# Hardware_Comp_V1_4.net
KiCad netlist of a schematic drawn in EAGLE
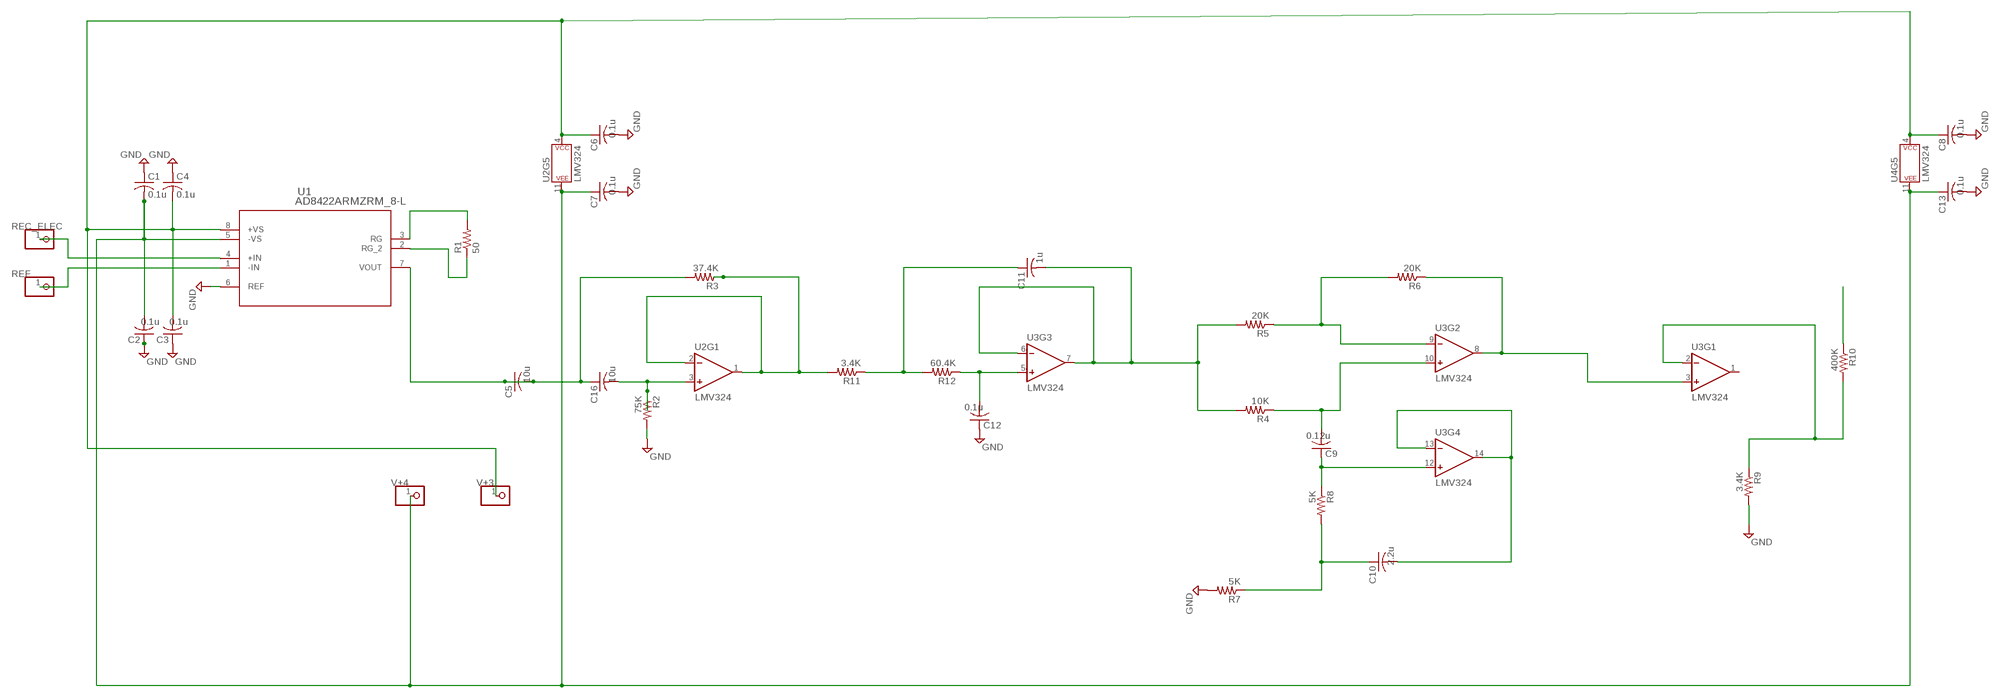
[diagram p0: schematic, sheet 1]

(export (version "E")
  (design (tool "Eeschema 10.0.6"))
  (components
    (comp (ref "9V-")
      (value "PINHD-1X1")
      (footprint "eagle-import:1X01")
      (libsource (lib "eagle-import") (part "PINHD-1X1"))
    )
    (comp (ref "C1")
      (value "0.1u")
      (footprint "eagle-import:C0603")
      (libsource (lib "eagle-import") (part "C-USC0603"))
    )
    (comp (ref "C2")
      (value "0.1u")
      (footprint "eagle-import:C0603")
      (libsource (lib "eagle-import") (part "C-USC0603"))
    )
    (comp (ref "C3")
      (value "0.1u")
      (footprint "eagle-import:C0603")
      (libsource (lib "eagle-import") (part "C-USC0603"))
    )
    (comp (ref "C4")
      (value "0.1u")
      (footprint "eagle-import:C0603")
      (libsource (lib "eagle-import") (part "C-USC0603"))
    )
    (comp (ref "C5")
      (value "10u")
      (footprint "eagle-import:C0603")
      (libsource (lib "eagle-import") (part "C-USC0603"))
    )
    (comp (ref "C6")
      (value "0.1u")
      (footprint "eagle-import:C0603")
      (libsource (lib "eagle-import") (part "C-USC0603"))
    )
    (comp (ref "C7")
      (value "0.1u")
      (footprint "eagle-import:C0603")
      (libsource (lib "eagle-import") (part "C-USC0603"))
    )
    (comp (ref "C8")
      (value "0.1u")
      (footprint "eagle-import:C0603")
      (libsource (lib "eagle-import") (part "C-USC0603"))
    )
    (comp (ref "C9")
      (value "0.12u")
      (footprint "eagle-import:C0603")
      (libsource (lib "eagle-import") (part "C-USC0603"))
    )
    (comp (ref "C10")
      (value "2.2u")
      (footprint "eagle-import:C0603")
      (libsource (lib "eagle-import") (part "C-USC0603"))
    )
    (comp (ref "C11")
      (value "1u")
      (footprint "eagle-import:C0603")
      (libsource (lib "eagle-import") (part "C-USC0603"))
    )
    (comp (ref "C12")
      (value "0.1u")
      (footprint "eagle-import:C0603")
      (libsource (lib "eagle-import") (part "C-USC0603"))
    )
    (comp (ref "C13")
      (value "0.1u")
      (footprint "eagle-import:C0603")
      (libsource (lib "eagle-import") (part "C-USC0603"))
    )
    (comp (ref "C16")
      (value "10u")
      (footprint "eagle-import:C0603")
      (libsource (lib "eagle-import") (part "C-USC0603"))
    )
    (comp (ref "JP1")
      (value "PINHD-1X1")
      (footprint "eagle-import:1X01")
      (libsource (lib "eagle-import") (part "PINHD-1X1"))
    )
    (comp (ref "JP2")
      (value "PINHD-1X1")
      (footprint "eagle-import:1X01")
      (libsource (lib "eagle-import") (part "PINHD-1X1"))
    )
    (comp (ref "JP3")
      (value "PINHD-1X1")
      (footprint "eagle-import:1X01")
      (libsource (lib "eagle-import") (part "PINHD-1X1"))
    )
    (comp (ref "R1")
      (value "50")
      (footprint "eagle-import:R0603")
      (libsource (lib "eagle-import") (part "R-US_R0603"))
    )
    (comp (ref "R2")
      (value "75K")
      (footprint "eagle-import:R0603")
      (libsource (lib "eagle-import") (part "R-US_R0603"))
    )
    (comp (ref "R3")
      (value "37.4K")
      (footprint "eagle-import:R0603")
      (libsource (lib "eagle-import") (part "R-US_R0603"))
    )
    (comp (ref "R4")
      (value "10K")
      (footprint "eagle-import:R0603")
      (libsource (lib "eagle-import") (part "R-US_R0603"))
    )
    (comp (ref "R5")
      (value "20K")
      (footprint "eagle-import:R0603")
      (libsource (lib "eagle-import") (part "R-US_R0603"))
    )
    (comp (ref "R6")
      (value "20K")
      (footprint "eagle-import:R0603")
      (libsource (lib "eagle-import") (part "R-US_R0603"))
    )
    (comp (ref "R7")
      (value "5K")
      (footprint "eagle-import:R0603")
      (libsource (lib "eagle-import") (part "R-US_R0603"))
    )
    (comp (ref "R8")
      (value "5K")
      (footprint "eagle-import:R0603")
      (libsource (lib "eagle-import") (part "R-US_R0603"))
    )
    (comp (ref "R9")
      (value "3.4K")
      (footprint "eagle-import:R0603")
      (libsource (lib "eagle-import") (part "R-US_R0603"))
    )
    (comp (ref "R10")
      (value "400K")
      (footprint "eagle-import:R0603")
      (libsource (lib "eagle-import") (part "R-US_R0603"))
    )
    (comp (ref "R11")
      (value "3.4K")
      (footprint "eagle-import:R0603")
      (libsource (lib "eagle-import") (part "R-US_R0603"))
    )
    (comp (ref "R12")
      (value "60.4K")
      (footprint "eagle-import:R0603")
      (libsource (lib "eagle-import") (part "R-US_R0603"))
    )
    (comp (ref "U1")
      (value "AD8422ARMZRM_8-L")
      (footprint "eagle-import:RM_8-L")
      (fields (field (name "MANUFACTURER_PART_NUMBER") "AD8422ARMZ"))
      (libsource (lib "eagle-import") (part "AD8422ARMZRM_8-L"))
    )
    (comp (ref "U2")
      (value "LMV324")
      (footprint "eagle-import:SO14")
      (libsource (lib "eagle-import") (part "LMV324"))
    )
    (comp (ref "U3")
      (value "LMV324")
      (footprint "eagle-import:SO14")
      (libsource (lib "eagle-import") (part "LMV324"))
    )
    (comp (ref "U4")
      (value "LMV324")
      (footprint "eagle-import:SO14")
      (libsource (lib "eagle-import") (part "LMV324"))
    )
  )
  (nets
    (net (code "1") (name "/REC_ELEC") (class "Default")
      (node (ref "JP1") (pin "1") (pinfunction "1_1") (pintype "passive"))
      (node (ref "U1") (pin "4") (pinfunction "+IN_4") (pintype "passive"))
    )
    (net (code "2") (name "/REF") (class "Default")
      (node (ref "JP2") (pin "1") (pinfunction "1_1") (pintype "passive"))
      (node (ref "U1") (pin "1") (pinfunction "-IN_1") (pintype "passive"))
    )
    (net (code "3") (name "/V+3") (class "Default")
      (node (ref "9V-") (pin "1") (pinfunction "1_1") (pintype "passive"))
      (node (ref "C3") (pin "2") (pinfunction "2_2") (pintype "passive"))
      (node (ref "C4") (pin "2") (pinfunction "2_2") (pintype "passive"))
      (node (ref "C6") (pin "1") (pinfunction "1_1") (pintype "passive"))
      (node (ref "C8") (pin "1") (pinfunction "1_1") (pintype "passive"))
      (node (ref "U1") (pin "8") (pinfunction "+VS_8") (pintype "passive"))
      (node (ref "U2") (pin "4") (pinfunction "P$V+_4") (pintype "bidirectional"))
      (node (ref "U4") (pin "4") (pinfunction "P$V+_4") (pintype "bidirectional"))
    )
    (net (code "4") (name "/V+4") (class "Default")
      (node (ref "C1") (pin "2") (pinfunction "2_2") (pintype "passive"))
      (node (ref "C13") (pin "1") (pinfunction "1_1") (pintype "passive"))
      (node (ref "C2") (pin "2") (pinfunction "2_2") (pintype "passive"))
      (node (ref "C7") (pin "1") (pinfunction "1_1") (pintype "passive"))
      (node (ref "JP3") (pin "1") (pinfunction "1_1") (pintype "passive"))
      (node (ref "U1") (pin "5") (pinfunction "-VS_5") (pintype "passive"))
      (node (ref "U2") (pin "11") (pinfunction "P$V-_11") (pintype "bidirectional"))
      (node (ref "U4") (pin "11") (pinfunction "P$V-_11") (pintype "bidirectional"))
    )
    (net (code "5") (name "GND") (class "Default")
      (node (ref "C1") (pin "1") (pinfunction "1_1") (pintype "passive"))
      (node (ref "C12") (pin "1") (pinfunction "1_1") (pintype "passive"))
      (node (ref "C13") (pin "2") (pinfunction "2_2") (pintype "passive"))
      (node (ref "C2") (pin "1") (pinfunction "1_1") (pintype "passive"))
      (node (ref "C3") (pin "1") (pinfunction "1_1") (pintype "passive"))
      (node (ref "C4") (pin "1") (pinfunction "1_1") (pintype "passive"))
      (node (ref "C6") (pin "2") (pinfunction "2_2") (pintype "passive"))
      (node (ref "C7") (pin "2") (pinfunction "2_2") (pintype "passive"))
      (node (ref "C8") (pin "2") (pinfunction "2_2") (pintype "passive"))
      (node (ref "R2") (pin "2") (pinfunction "2_2") (pintype "passive"))
      (node (ref "R7") (pin "2") (pinfunction "2_2") (pintype "passive"))
      (node (ref "R9") (pin "2") (pinfunction "2_2") (pintype "passive"))
      (node (ref "U1") (pin "6") (pinfunction "REF_6") (pintype "passive"))
    )
    (net (code "6") (name "Net-(C10-Pad1)") (class "Default")
      (node (ref "C10") (pin "1") (pinfunction "1_1") (pintype "passive"))
      (node (ref "R7") (pin "1") (pinfunction "1_1") (pintype "passive"))
      (node (ref "R8") (pin "2") (pinfunction "2_2") (pintype "passive"))
    )
    (net (code "7") (name "Net-(C11-Pad1)") (class "Default")
      (node (ref "C11") (pin "1") (pinfunction "1_1") (pintype "passive"))
      (node (ref "R11") (pin "1") (pinfunction "1_1") (pintype "passive"))
      (node (ref "R12") (pin "2") (pinfunction "2_2") (pintype "passive"))
    )
    (net (code "8") (name "Net-(U1-RG)") (class "Default")
      (node (ref "R1") (pin "2") (pinfunction "2_2") (pintype "passive"))
      (node (ref "U1") (pin "3") (pinfunction "RG_3") (pintype "passive"))
    )
    (net (code "9") (name "Net-(U1-RG_2)") (class "Default")
      (node (ref "R1") (pin "1") (pinfunction "1_1") (pintype "passive"))
      (node (ref "U1") (pin "2") (pinfunction "RG_2_2") (pintype "passive"))
    )
    (net (code "10") (name "Net-(U1-VOUT)") (class "Default")
      (node (ref "C16") (pin "1") (pinfunction "1_1") (pintype "passive"))
      (node (ref "C5") (pin "1") (pinfunction "1_1") (pintype "passive"))
      (node (ref "C5") (pin "2") (pinfunction "2_2") (pintype "passive"))
      (node (ref "R3") (pin "2") (pinfunction "2_2") (pintype "passive"))
      (node (ref "U1") (pin "7") (pinfunction "VOUT_7") (pintype "passive"))
    )
    (net (code "11") (name "Net-(U2A-+IN)") (class "Default")
      (node (ref "C16") (pin "2") (pinfunction "2_2") (pintype "passive"))
      (node (ref "R2") (pin "1") (pinfunction "1_1") (pintype "passive"))
      (node (ref "U2") (pin "3") (pinfunction "+IN_3") (pintype "input"))
    )
    (net (code "12") (name "Net-(U2A--IN)") (class "Default")
      (node (ref "R11") (pin "2") (pinfunction "2_2") (pintype "passive"))
      (node (ref "R3") (pin "1") (pinfunction "1_1") (pintype "passive"))
      (node (ref "U2") (pin "1") (pinfunction "OUT_1") (pintype "output"))
      (node (ref "U2") (pin "2") (pinfunction "-IN_2") (pintype "input"))
    )
    (net (code "13") (name "Net-(U3A-+IN)") (class "Default")
      (node (ref "R6") (pin "1") (pinfunction "1_1") (pintype "passive"))
      (node (ref "U3") (pin "3") (pinfunction "+IN_3") (pintype "input"))
      (node (ref "U3") (pin "8") (pinfunction "OUT_8") (pintype "output"))
    )
    (net (code "14") (name "Net-(U3A--IN)") (class "Default")
      (node (ref "R10") (pin "2") (pinfunction "2_2") (pintype "passive"))
      (node (ref "R9") (pin "1") (pinfunction "1_1") (pintype "passive"))
      (node (ref "U3") (pin "2") (pinfunction "-IN_2") (pintype "input"))
    )
    (net (code "15") (name "Net-(U3B-+IN)") (class "Default")
      (node (ref "C9") (pin "2") (pinfunction "2_2") (pintype "passive"))
      (node (ref "R4") (pin "1") (pinfunction "1_1") (pintype "passive"))
      (node (ref "U3") (pin "10") (pinfunction "+IN_10") (pintype "input"))
    )
    (net (code "16") (name "Net-(U3B--IN)") (class "Default")
      (node (ref "R5") (pin "1") (pinfunction "1_1") (pintype "passive"))
      (node (ref "R6") (pin "2") (pinfunction "2_2") (pintype "passive"))
      (node (ref "U3") (pin "9") (pinfunction "-IN_9") (pintype "input"))
    )
    (net (code "17") (name "Net-(U3C-+IN)") (class "Default")
      (node (ref "C12") (pin "2") (pinfunction "2_2") (pintype "passive"))
      (node (ref "R12") (pin "1") (pinfunction "1_1") (pintype "passive"))
      (node (ref "U3") (pin "5") (pinfunction "+IN_5") (pintype "input"))
    )
    (net (code "18") (name "Net-(U3C--IN)") (class "Default")
      (node (ref "C11") (pin "2") (pinfunction "2_2") (pintype "passive"))
      (node (ref "R4") (pin "2") (pinfunction "2_2") (pintype "passive"))
      (node (ref "R5") (pin "2") (pinfunction "2_2") (pintype "passive"))
      (node (ref "U3") (pin "6") (pinfunction "-IN_6") (pintype "input"))
      (node (ref "U3") (pin "7") (pinfunction "OUT_7") (pintype "output"))
    )
    (net (code "19") (name "Net-(U3D-+IN)") (class "Default")
      (node (ref "C9") (pin "1") (pinfunction "1_1") (pintype "passive"))
      (node (ref "R8") (pin "1") (pinfunction "1_1") (pintype "passive"))
      (node (ref "U3") (pin "12") (pinfunction "+IN_12") (pintype "input"))
    )
    (net (code "20") (name "Net-(U3D--IN)") (class "Default")
      (node (ref "C10") (pin "2") (pinfunction "2_2") (pintype "passive"))
      (node (ref "U3") (pin "13") (pinfunction "-IN_13") (pintype "input"))
      (node (ref "U3") (pin "14") (pinfunction "OUT_14") (pintype "output"))
    )
    (net (code "21") (name "unconnected-(R10-Pad1)") (class "Default")
      (node (ref "R10") (pin "1") (pinfunction "1_1") (pintype "passive"))
    )
    (net (code "22") (name "unconnected-(U3A-OUT-Pad1)") (class "Default")
      (node (ref "U3") (pin "1") (pinfunction "OUT_1") (pintype "output"))
    )
  )
)
